# SCH_SEGEMENTOS_HORA_1.net
KiCad netlist of a schematic drawn in Altium Designer
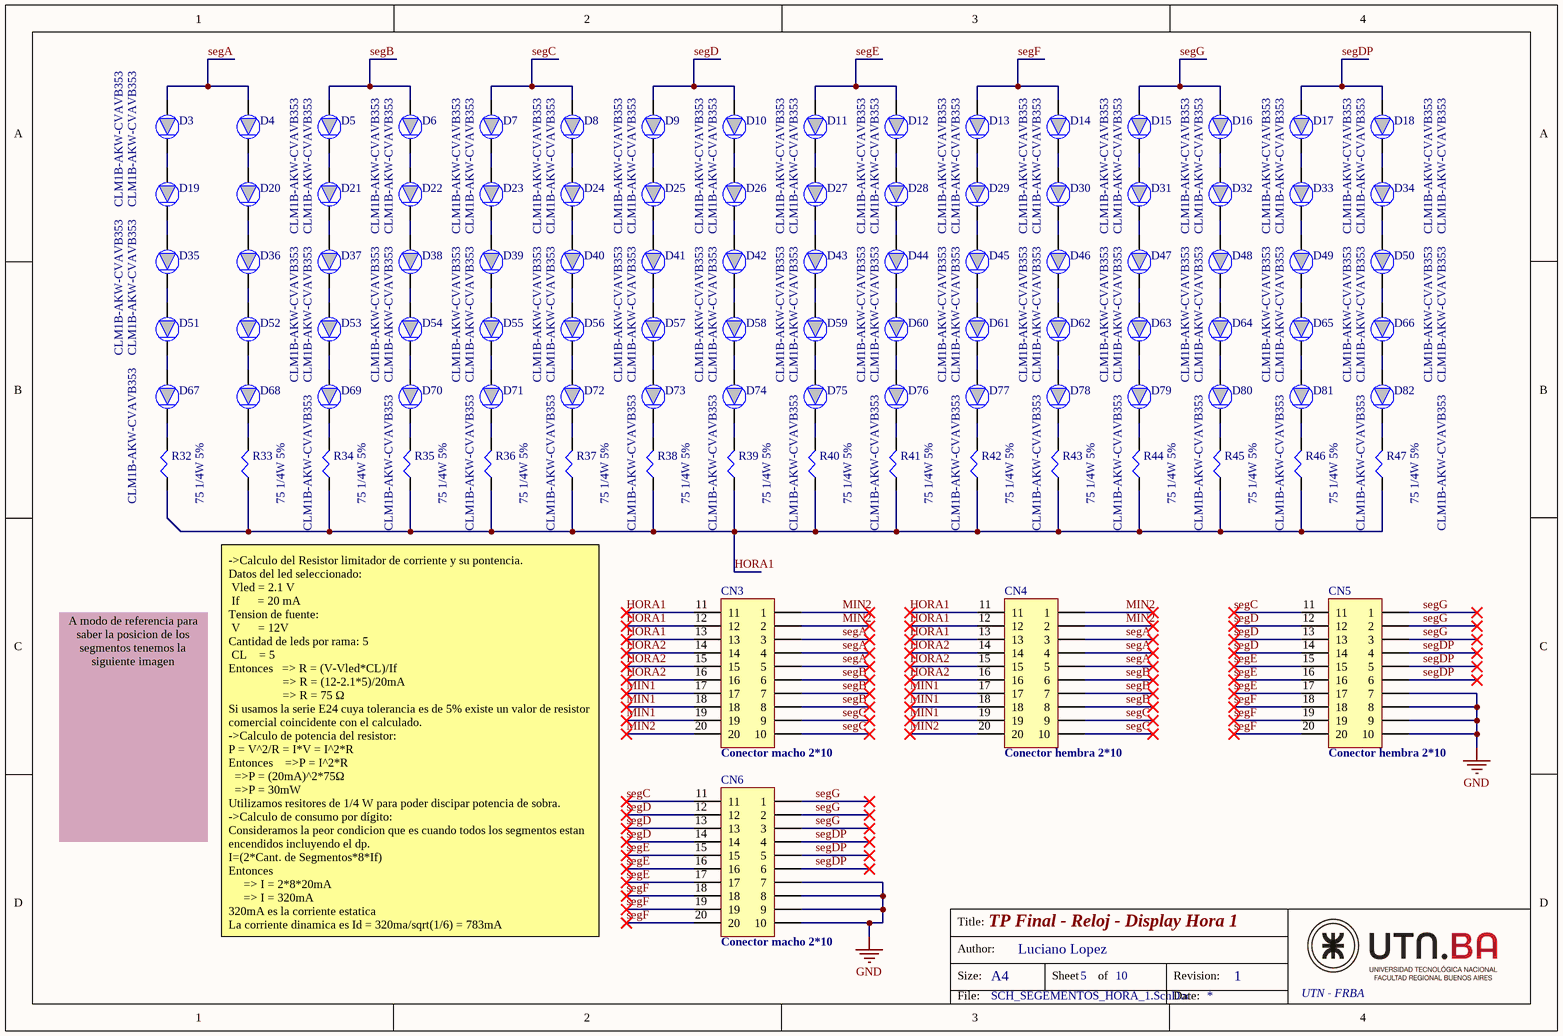
[diagram p0: SCH_SEGEMENTOS_HORA_1.SchDoc]

(export (version "E")
  (design (tool "Eeschema 10.0.6"))
  (components
    (comp (ref "CN3")
      (value "Conector macho 2*10")
      (description "Connector Generic 10 Vias")
      (libsource (lib "SCH_LIB") (part "CONN_2x10P"))
    )
    (comp (ref "CN4")
      (value "Conector hembra 2*10")
      (description "Connector Generic 10 Vias")
      (libsource (lib "SCH_LIB") (part "CONN_2x10P"))
    )
    (comp (ref "CN5")
      (value "Conector hembra 2*10")
      (description "Connector Generic 10 Vias")
      (libsource (lib "SCH_LIB") (part "CONN_2x10P"))
    )
    (comp (ref "CN6")
      (value "Conector macho 2*10")
      (description "Connector Generic 10 Vias")
      (libsource (lib "SCH_LIB") (part "CONN_2x10P"))
    )
    (comp (ref "D3")
      (value "CLM1B-AKW-CVAVB353")
      (footprint "PLCC2_LED")
      (libsource (lib "SCH_LIB") (part "LED_DIODE"))
    )
    (comp (ref "D4")
      (value "CLM1B-AKW-CVAVB353")
      (footprint "PLCC2_LED")
      (libsource (lib "SCH_LIB") (part "LED_DIODE"))
    )
    (comp (ref "D5")
      (value "CLM1B-AKW-CVAVB353")
      (footprint "PLCC2_LED")
      (libsource (lib "SCH_LIB") (part "LED_DIODE"))
    )
    (comp (ref "D6")
      (value "CLM1B-AKW-CVAVB353")
      (footprint "PLCC2_LED")
      (libsource (lib "SCH_LIB") (part "LED_DIODE"))
    )
    (comp (ref "D7")
      (value "CLM1B-AKW-CVAVB353")
      (footprint "PLCC2_LED")
      (libsource (lib "SCH_LIB") (part "LED_DIODE"))
    )
    (comp (ref "D8")
      (value "CLM1B-AKW-CVAVB353")
      (footprint "PLCC2_LED")
      (libsource (lib "SCH_LIB") (part "LED_DIODE"))
    )
    (comp (ref "D9")
      (value "CLM1B-AKW-CVAVB353")
      (footprint "PLCC2_LED")
      (libsource (lib "SCH_LIB") (part "LED_DIODE"))
    )
    (comp (ref "D10")
      (value "CLM1B-AKW-CVAVB353")
      (footprint "PLCC2_LED")
      (libsource (lib "SCH_LIB") (part "LED_DIODE"))
    )
    (comp (ref "D11")
      (value "CLM1B-AKW-CVAVB353")
      (footprint "PLCC2_LED")
      (libsource (lib "SCH_LIB") (part "LED_DIODE"))
    )
    (comp (ref "D12")
      (value "CLM1B-AKW-CVAVB353")
      (footprint "PLCC2_LED")
      (libsource (lib "SCH_LIB") (part "LED_DIODE"))
    )
    (comp (ref "D13")
      (value "CLM1B-AKW-CVAVB353")
      (footprint "PLCC2_LED")
      (libsource (lib "SCH_LIB") (part "LED_DIODE"))
    )
    (comp (ref "D14")
      (value "CLM1B-AKW-CVAVB353")
      (footprint "PLCC2_LED")
      (libsource (lib "SCH_LIB") (part "LED_DIODE"))
    )
    (comp (ref "D15")
      (value "CLM1B-AKW-CVAVB353")
      (footprint "PLCC2_LED")
      (libsource (lib "SCH_LIB") (part "LED_DIODE"))
    )
    (comp (ref "D16")
      (value "CLM1B-AKW-CVAVB353")
      (footprint "PLCC2_LED")
      (libsource (lib "SCH_LIB") (part "LED_DIODE"))
    )
    (comp (ref "D17")
      (value "CLM1B-AKW-CVAVB353")
      (footprint "PLCC2_LED")
      (libsource (lib "SCH_LIB") (part "LED_DIODE"))
    )
    (comp (ref "D18")
      (value "CLM1B-AKW-CVAVB353")
      (footprint "PLCC2_LED")
      (libsource (lib "SCH_LIB") (part "LED_DIODE"))
    )
    (comp (ref "D19")
      (value "CLM1B-AKW-CVAVB353")
      (footprint "PLCC2_LED")
      (libsource (lib "SCH_LIB") (part "LED_DIODE"))
    )
    (comp (ref "D20")
      (value "CLM1B-AKW-CVAVB353")
      (footprint "PLCC2_LED")
      (libsource (lib "SCH_LIB") (part "LED_DIODE"))
    )
    (comp (ref "D21")
      (value "CLM1B-AKW-CVAVB353")
      (footprint "PLCC2_LED")
      (libsource (lib "SCH_LIB") (part "LED_DIODE"))
    )
    (comp (ref "D22")
      (value "CLM1B-AKW-CVAVB353")
      (footprint "PLCC2_LED")
      (libsource (lib "SCH_LIB") (part "LED_DIODE"))
    )
    (comp (ref "D23")
      (value "CLM1B-AKW-CVAVB353")
      (footprint "PLCC2_LED")
      (libsource (lib "SCH_LIB") (part "LED_DIODE"))
    )
    (comp (ref "D24")
      (value "CLM1B-AKW-CVAVB353")
      (footprint "PLCC2_LED")
      (libsource (lib "SCH_LIB") (part "LED_DIODE"))
    )
    (comp (ref "D25")
      (value "CLM1B-AKW-CVAVB353")
      (footprint "PLCC2_LED")
      (libsource (lib "SCH_LIB") (part "LED_DIODE"))
    )
    (comp (ref "D26")
      (value "CLM1B-AKW-CVAVB353")
      (footprint "PLCC2_LED")
      (libsource (lib "SCH_LIB") (part "LED_DIODE"))
    )
    (comp (ref "D27")
      (value "CLM1B-AKW-CVAVB353")
      (footprint "PLCC2_LED")
      (libsource (lib "SCH_LIB") (part "LED_DIODE"))
    )
    (comp (ref "D28")
      (value "CLM1B-AKW-CVAVB353")
      (footprint "PLCC2_LED")
      (libsource (lib "SCH_LIB") (part "LED_DIODE"))
    )
    (comp (ref "D29")
      (value "CLM1B-AKW-CVAVB353")
      (footprint "PLCC2_LED")
      (libsource (lib "SCH_LIB") (part "LED_DIODE"))
    )
    (comp (ref "D30")
      (value "CLM1B-AKW-CVAVB353")
      (footprint "PLCC2_LED")
      (libsource (lib "SCH_LIB") (part "LED_DIODE"))
    )
    (comp (ref "D31")
      (value "CLM1B-AKW-CVAVB353")
      (footprint "PLCC2_LED")
      (libsource (lib "SCH_LIB") (part "LED_DIODE"))
    )
    (comp (ref "D32")
      (value "CLM1B-AKW-CVAVB353")
      (footprint "PLCC2_LED")
      (libsource (lib "SCH_LIB") (part "LED_DIODE"))
    )
    (comp (ref "D33")
      (value "CLM1B-AKW-CVAVB353")
      (footprint "PLCC2_LED")
      (libsource (lib "SCH_LIB") (part "LED_DIODE"))
    )
    (comp (ref "D34")
      (value "CLM1B-AKW-CVAVB353")
      (footprint "PLCC2_LED")
      (libsource (lib "SCH_LIB") (part "LED_DIODE"))
    )
    (comp (ref "D35")
      (value "CLM1B-AKW-CVAVB353")
      (footprint "PLCC2_LED")
      (libsource (lib "SCH_LIB") (part "LED_DIODE"))
    )
    (comp (ref "D36")
      (value "CLM1B-AKW-CVAVB353")
      (footprint "PLCC2_LED")
      (libsource (lib "SCH_LIB") (part "LED_DIODE"))
    )
    (comp (ref "D37")
      (value "CLM1B-AKW-CVAVB353")
      (footprint "PLCC2_LED")
      (libsource (lib "SCH_LIB") (part "LED_DIODE"))
    )
    (comp (ref "D38")
      (value "CLM1B-AKW-CVAVB353")
      (footprint "PLCC2_LED")
      (libsource (lib "SCH_LIB") (part "LED_DIODE"))
    )
    (comp (ref "D39")
      (value "CLM1B-AKW-CVAVB353")
      (footprint "PLCC2_LED")
      (libsource (lib "SCH_LIB") (part "LED_DIODE"))
    )
    (comp (ref "D40")
      (value "CLM1B-AKW-CVAVB353")
      (footprint "PLCC2_LED")
      (libsource (lib "SCH_LIB") (part "LED_DIODE"))
    )
    (comp (ref "D41")
      (value "CLM1B-AKW-CVAVB353")
      (footprint "PLCC2_LED")
      (libsource (lib "SCH_LIB") (part "LED_DIODE"))
    )
    (comp (ref "D42")
      (value "CLM1B-AKW-CVAVB353")
      (footprint "PLCC2_LED")
      (libsource (lib "SCH_LIB") (part "LED_DIODE"))
    )
    (comp (ref "D43")
      (value "CLM1B-AKW-CVAVB353")
      (footprint "PLCC2_LED")
      (libsource (lib "SCH_LIB") (part "LED_DIODE"))
    )
    (comp (ref "D44")
      (value "CLM1B-AKW-CVAVB353")
      (footprint "PLCC2_LED")
      (libsource (lib "SCH_LIB") (part "LED_DIODE"))
    )
    (comp (ref "D45")
      (value "CLM1B-AKW-CVAVB353")
      (footprint "PLCC2_LED")
      (libsource (lib "SCH_LIB") (part "LED_DIODE"))
    )
    (comp (ref "D46")
      (value "CLM1B-AKW-CVAVB353")
      (footprint "PLCC2_LED")
      (libsource (lib "SCH_LIB") (part "LED_DIODE"))
    )
    (comp (ref "D47")
      (value "CLM1B-AKW-CVAVB353")
      (footprint "PLCC2_LED")
      (libsource (lib "SCH_LIB") (part "LED_DIODE"))
    )
    (comp (ref "D48")
      (value "CLM1B-AKW-CVAVB353")
      (footprint "PLCC2_LED")
      (libsource (lib "SCH_LIB") (part "LED_DIODE"))
    )
    (comp (ref "D49")
      (value "CLM1B-AKW-CVAVB353")
      (footprint "PLCC2_LED")
      (libsource (lib "SCH_LIB") (part "LED_DIODE"))
    )
    (comp (ref "D50")
      (value "CLM1B-AKW-CVAVB353")
      (footprint "PLCC2_LED")
      (libsource (lib "SCH_LIB") (part "LED_DIODE"))
    )
    (comp (ref "D51")
      (value "CLM1B-AKW-CVAVB353")
      (footprint "PLCC2_LED")
      (libsource (lib "SCH_LIB") (part "LED_DIODE"))
    )
    (comp (ref "D52")
      (value "CLM1B-AKW-CVAVB353")
      (footprint "PLCC2_LED")
      (libsource (lib "SCH_LIB") (part "LED_DIODE"))
    )
    (comp (ref "D53")
      (value "CLM1B-AKW-CVAVB353")
      (footprint "PLCC2_LED")
      (libsource (lib "SCH_LIB") (part "LED_DIODE"))
    )
    (comp (ref "D54")
      (value "CLM1B-AKW-CVAVB353")
      (footprint "PLCC2_LED")
      (libsource (lib "SCH_LIB") (part "LED_DIODE"))
    )
    (comp (ref "D55")
      (value "CLM1B-AKW-CVAVB353")
      (footprint "PLCC2_LED")
      (libsource (lib "SCH_LIB") (part "LED_DIODE"))
    )
    (comp (ref "D56")
      (value "CLM1B-AKW-CVAVB353")
      (footprint "PLCC2_LED")
      (libsource (lib "SCH_LIB") (part "LED_DIODE"))
    )
    (comp (ref "D57")
      (value "CLM1B-AKW-CVAVB353")
      (footprint "PLCC2_LED")
      (libsource (lib "SCH_LIB") (part "LED_DIODE"))
    )
    (comp (ref "D58")
      (value "CLM1B-AKW-CVAVB353")
      (footprint "PLCC2_LED")
      (libsource (lib "SCH_LIB") (part "LED_DIODE"))
    )
    (comp (ref "D59")
      (value "CLM1B-AKW-CVAVB353")
      (footprint "PLCC2_LED")
      (libsource (lib "SCH_LIB") (part "LED_DIODE"))
    )
    (comp (ref "D60")
      (value "CLM1B-AKW-CVAVB353")
      (footprint "PLCC2_LED")
      (libsource (lib "SCH_LIB") (part "LED_DIODE"))
    )
    (comp (ref "D61")
      (value "CLM1B-AKW-CVAVB353")
      (footprint "PLCC2_LED")
      (libsource (lib "SCH_LIB") (part "LED_DIODE"))
    )
    (comp (ref "D62")
      (value "CLM1B-AKW-CVAVB353")
      (footprint "PLCC2_LED")
      (libsource (lib "SCH_LIB") (part "LED_DIODE"))
    )
    (comp (ref "D63")
      (value "CLM1B-AKW-CVAVB353")
      (footprint "PLCC2_LED")
      (libsource (lib "SCH_LIB") (part "LED_DIODE"))
    )
    (comp (ref "D64")
      (value "CLM1B-AKW-CVAVB353")
      (footprint "PLCC2_LED")
      (libsource (lib "SCH_LIB") (part "LED_DIODE"))
    )
    (comp (ref "D65")
      (value "CLM1B-AKW-CVAVB353")
      (footprint "PLCC2_LED")
      (libsource (lib "SCH_LIB") (part "LED_DIODE"))
    )
    (comp (ref "D66")
      (value "CLM1B-AKW-CVAVB353")
      (footprint "PLCC2_LED")
      (libsource (lib "SCH_LIB") (part "LED_DIODE"))
    )
    (comp (ref "D67")
      (value "CLM1B-AKW-CVAVB353")
      (footprint "PLCC2_LED")
      (libsource (lib "SCH_LIB") (part "LED_DIODE"))
    )
    (comp (ref "D68")
      (value "CLM1B-AKW-CVAVB353")
      (footprint "PLCC2_LED")
      (libsource (lib "SCH_LIB") (part "LED_DIODE"))
    )
    (comp (ref "D69")
      (value "CLM1B-AKW-CVAVB353")
      (footprint "PLCC2_LED")
      (libsource (lib "SCH_LIB") (part "LED_DIODE"))
    )
    (comp (ref "D70")
      (value "CLM1B-AKW-CVAVB353")
      (footprint "PLCC2_LED")
      (libsource (lib "SCH_LIB") (part "LED_DIODE"))
    )
    (comp (ref "D71")
      (value "CLM1B-AKW-CVAVB353")
      (footprint "PLCC2_LED")
      (libsource (lib "SCH_LIB") (part "LED_DIODE"))
    )
    (comp (ref "D72")
      (value "CLM1B-AKW-CVAVB353")
      (footprint "PLCC2_LED")
      (libsource (lib "SCH_LIB") (part "LED_DIODE"))
    )
    (comp (ref "D73")
      (value "CLM1B-AKW-CVAVB353")
      (footprint "PLCC2_LED")
      (libsource (lib "SCH_LIB") (part "LED_DIODE"))
    )
    (comp (ref "D74")
      (value "CLM1B-AKW-CVAVB353")
      (footprint "PLCC2_LED")
      (libsource (lib "SCH_LIB") (part "LED_DIODE"))
    )
    (comp (ref "D75")
      (value "CLM1B-AKW-CVAVB353")
      (footprint "PLCC2_LED")
      (libsource (lib "SCH_LIB") (part "LED_DIODE"))
    )
    (comp (ref "D76")
      (value "CLM1B-AKW-CVAVB353")
      (footprint "PLCC2_LED")
      (libsource (lib "SCH_LIB") (part "LED_DIODE"))
    )
    (comp (ref "D77")
      (value "CLM1B-AKW-CVAVB353")
      (footprint "PLCC2_LED")
      (libsource (lib "SCH_LIB") (part "LED_DIODE"))
    )
    (comp (ref "D78")
      (value "CLM1B-AKW-CVAVB353")
      (footprint "PLCC2_LED")
      (libsource (lib "SCH_LIB") (part "LED_DIODE"))
    )
    (comp (ref "D79")
      (value "CLM1B-AKW-CVAVB353")
      (footprint "PLCC2_LED")
      (libsource (lib "SCH_LIB") (part "LED_DIODE"))
    )
    (comp (ref "D80")
      (value "CLM1B-AKW-CVAVB353")
      (footprint "PLCC2_LED")
      (libsource (lib "SCH_LIB") (part "LED_DIODE"))
    )
    (comp (ref "D81")
      (value "CLM1B-AKW-CVAVB353")
      (footprint "PLCC2_LED")
      (libsource (lib "SCH_LIB") (part "LED_DIODE"))
    )
    (comp (ref "D82")
      (value "CLM1B-AKW-CVAVB353")
      (footprint "PLCC2_LED")
      (libsource (lib "SCH_LIB") (part "LED_DIODE"))
    )
    (comp (ref "R32") (value "75 1/4W 5%") (footprint "R_0805") (libsource (lib "SCH_LIB") (part "Resistor")))
    (comp (ref "R33") (value "75 1/4W 5%") (footprint "R_0805") (libsource (lib "SCH_LIB") (part "Resistor")))
    (comp (ref "R34") (value "75 1/4W 5%") (footprint "R_0805") (libsource (lib "SCH_LIB") (part "Resistor")))
    (comp (ref "R35") (value "75 1/4W 5%") (footprint "R_0805") (libsource (lib "SCH_LIB") (part "Resistor")))
    (comp (ref "R36") (value "75 1/4W 5%") (footprint "R_0805") (libsource (lib "SCH_LIB") (part "Resistor")))
    (comp (ref "R37") (value "75 1/4W 5%") (footprint "R_0805") (libsource (lib "SCH_LIB") (part "Resistor")))
    (comp (ref "R38") (value "75 1/4W 5%") (footprint "R_0805") (libsource (lib "SCH_LIB") (part "Resistor")))
    (comp (ref "R39") (value "75 1/4W 5%") (footprint "R_0805") (libsource (lib "SCH_LIB") (part "Resistor")))
    (comp (ref "R40") (value "75 1/4W 5%") (footprint "R_0805") (libsource (lib "SCH_LIB") (part "Resistor")))
    (comp (ref "R41") (value "75 1/4W 5%") (footprint "R_0805") (libsource (lib "SCH_LIB") (part "Resistor")))
    (comp (ref "R42") (value "75 1/4W 5%") (footprint "R_0805") (libsource (lib "SCH_LIB") (part "Resistor")))
    (comp (ref "R43") (value "75 1/4W 5%") (footprint "R_0805") (libsource (lib "SCH_LIB") (part "Resistor")))
    (comp (ref "R44") (value "75 1/4W 5%") (footprint "R_0805") (libsource (lib "SCH_LIB") (part "Resistor")))
    (comp (ref "R45") (value "75 1/4W 5%") (footprint "R_0805") (libsource (lib "SCH_LIB") (part "Resistor")))
    (comp (ref "R46") (value "75 1/4W 5%") (footprint "R_0805") (libsource (lib "SCH_LIB") (part "Resistor")))
    (comp (ref "R47") (value "75 1/4W 5%") (footprint "R_0805") (libsource (lib "SCH_LIB") (part "Resistor")))
  )
  (nets
    (net (code "1") (name "/HORA1") (class "Default")
      (node (ref "CN3") (pin "11") (pinfunction "11_11") (pintype "passive"))
      (node (ref "CN3") (pin "12") (pinfunction "12_12") (pintype "passive"))
      (node (ref "CN3") (pin "13") (pinfunction "13_13") (pintype "passive"))
      (node (ref "CN4") (pin "11") (pinfunction "11_11") (pintype "passive"))
      (node (ref "CN4") (pin "12") (pinfunction "12_12") (pintype "passive"))
      (node (ref "CN4") (pin "13") (pinfunction "13_13") (pintype "passive"))
      (node (ref "R32") (pin "47") (pinfunction "47_47") (pintype "passive"))
      (node (ref "R33") (pin "47") (pinfunction "47_47") (pintype "passive"))
      (node (ref "R34") (pin "47") (pinfunction "47_47") (pintype "passive"))
      (node (ref "R35") (pin "47") (pinfunction "47_47") (pintype "passive"))
      (node (ref "R36") (pin "47") (pinfunction "47_47") (pintype "passive"))
      (node (ref "R37") (pin "47") (pinfunction "47_47") (pintype "passive"))
      (node (ref "R38") (pin "47") (pinfunction "47_47") (pintype "passive"))
      (node (ref "R39") (pin "47") (pinfunction "47_47") (pintype "passive"))
      (node (ref "R40") (pin "47") (pinfunction "47_47") (pintype "passive"))
      (node (ref "R41") (pin "47") (pinfunction "47_47") (pintype "passive"))
      (node (ref "R42") (pin "47") (pinfunction "47_47") (pintype "passive"))
      (node (ref "R43") (pin "47") (pinfunction "47_47") (pintype "passive"))
      (node (ref "R44") (pin "47") (pinfunction "47_47") (pintype "passive"))
      (node (ref "R45") (pin "47") (pinfunction "47_47") (pintype "passive"))
      (node (ref "R46") (pin "47") (pinfunction "47_47") (pintype "passive"))
      (node (ref "R47") (pin "47") (pinfunction "47_47") (pintype "passive"))
    )
    (net (code "2") (name "/HORA2") (class "Default")
      (node (ref "CN3") (pin "14") (pinfunction "14_14") (pintype "passive"))
      (node (ref "CN3") (pin "15") (pinfunction "15_15") (pintype "passive"))
      (node (ref "CN3") (pin "16") (pinfunction "16_16") (pintype "passive"))
      (node (ref "CN4") (pin "14") (pinfunction "14_14") (pintype "passive"))
      (node (ref "CN4") (pin "15") (pinfunction "15_15") (pintype "passive"))
      (node (ref "CN4") (pin "16") (pinfunction "16_16") (pintype "passive"))
    )
    (net (code "3") (name "/MIN1") (class "Default")
      (node (ref "CN3") (pin "17") (pinfunction "17_17") (pintype "passive"))
      (node (ref "CN3") (pin "18") (pinfunction "18_18") (pintype "passive"))
      (node (ref "CN3") (pin "19") (pinfunction "19_19") (pintype "passive"))
      (node (ref "CN4") (pin "17") (pinfunction "17_17") (pintype "passive"))
      (node (ref "CN4") (pin "18") (pinfunction "18_18") (pintype "passive"))
      (node (ref "CN4") (pin "19") (pinfunction "19_19") (pintype "passive"))
    )
    (net (code "4") (name "/MIN2") (class "Default")
      (node (ref "CN3") (pin "1") (pinfunction "1_1") (pintype "passive"))
      (node (ref "CN3") (pin "2") (pinfunction "2_2") (pintype "passive"))
      (node (ref "CN3") (pin "20") (pinfunction "20_20") (pintype "passive"))
      (node (ref "CN4") (pin "1") (pinfunction "1_1") (pintype "passive"))
      (node (ref "CN4") (pin "2") (pinfunction "2_2") (pintype "passive"))
      (node (ref "CN4") (pin "20") (pinfunction "20_20") (pintype "passive"))
    )
    (net (code "5") (name "/segA") (class "Default")
      (node (ref "CN3") (pin "3") (pinfunction "3_3") (pintype "passive"))
      (node (ref "CN3") (pin "4") (pinfunction "4_4") (pintype "passive"))
      (node (ref "CN3") (pin "5") (pinfunction "5_5") (pintype "passive"))
      (node (ref "CN4") (pin "3") (pinfunction "3_3") (pintype "passive"))
      (node (ref "CN4") (pin "4") (pinfunction "4_4") (pintype "passive"))
      (node (ref "CN4") (pin "5") (pinfunction "5_5") (pintype "passive"))
      (node (ref "D3") (pin "12") (pinfunction "12_12") (pintype "passive"))
      (node (ref "D4") (pin "12") (pinfunction "12_12") (pintype "passive"))
    )
    (net (code "6") (name "/segB") (class "Default")
      (node (ref "CN3") (pin "6") (pinfunction "6_6") (pintype "passive"))
      (node (ref "CN3") (pin "7") (pinfunction "7_7") (pintype "passive"))
      (node (ref "CN3") (pin "8") (pinfunction "8_8") (pintype "passive"))
      (node (ref "CN4") (pin "6") (pinfunction "6_6") (pintype "passive"))
      (node (ref "CN4") (pin "7") (pinfunction "7_7") (pintype "passive"))
      (node (ref "CN4") (pin "8") (pinfunction "8_8") (pintype "passive"))
      (node (ref "D5") (pin "12") (pinfunction "12_12") (pintype "passive"))
      (node (ref "D6") (pin "12") (pinfunction "12_12") (pintype "passive"))
    )
    (net (code "7") (name "/segC") (class "Default")
      (node (ref "CN3") (pin "10") (pinfunction "10_10") (pintype "passive"))
      (node (ref "CN3") (pin "9") (pinfunction "9_9") (pintype "passive"))
      (node (ref "CN4") (pin "10") (pinfunction "10_10") (pintype "passive"))
      (node (ref "CN4") (pin "9") (pinfunction "9_9") (pintype "passive"))
      (node (ref "CN5") (pin "11") (pinfunction "11_11") (pintype "passive"))
      (node (ref "CN6") (pin "11") (pinfunction "11_11") (pintype "passive"))
      (node (ref "D7") (pin "12") (pinfunction "12_12") (pintype "passive"))
      (node (ref "D8") (pin "12") (pinfunction "12_12") (pintype "passive"))
    )
    (net (code "8") (name "/segD") (class "Default")
      (node (ref "CN5") (pin "12") (pinfunction "12_12") (pintype "passive"))
      (node (ref "CN5") (pin "13") (pinfunction "13_13") (pintype "passive"))
      (node (ref "CN5") (pin "14") (pinfunction "14_14") (pintype "passive"))
      (node (ref "CN6") (pin "12") (pinfunction "12_12") (pintype "passive"))
      (node (ref "CN6") (pin "13") (pinfunction "13_13") (pintype "passive"))
      (node (ref "CN6") (pin "14") (pinfunction "14_14") (pintype "passive"))
      (node (ref "D10") (pin "12") (pinfunction "12_12") (pintype "passive"))
      (node (ref "D9") (pin "12") (pinfunction "12_12") (pintype "passive"))
    )
    (net (code "9") (name "/segDP") (class "Default")
      (node (ref "CN5") (pin "4") (pinfunction "4_4") (pintype "passive"))
      (node (ref "CN5") (pin "5") (pinfunction "5_5") (pintype "passive"))
      (node (ref "CN5") (pin "6") (pinfunction "6_6") (pintype "passive"))
      (node (ref "CN6") (pin "4") (pinfunction "4_4") (pintype "passive"))
      (node (ref "CN6") (pin "5") (pinfunction "5_5") (pintype "passive"))
      (node (ref "CN6") (pin "6") (pinfunction "6_6") (pintype "passive"))
      (node (ref "D17") (pin "12") (pinfunction "12_12") (pintype "passive"))
      (node (ref "D18") (pin "12") (pinfunction "12_12") (pintype "passive"))
    )
    (net (code "10") (name "/segE") (class "Default")
      (node (ref "CN5") (pin "15") (pinfunction "15_15") (pintype "passive"))
      (node (ref "CN5") (pin "16") (pinfunction "16_16") (pintype "passive"))
      (node (ref "CN5") (pin "17") (pinfunction "17_17") (pintype "passive"))
      (node (ref "CN6") (pin "15") (pinfunction "15_15") (pintype "passive"))
      (node (ref "CN6") (pin "16") (pinfunction "16_16") (pintype "passive"))
      (node (ref "CN6") (pin "17") (pinfunction "17_17") (pintype "passive"))
      (node (ref "D11") (pin "12") (pinfunction "12_12") (pintype "passive"))
      (node (ref "D12") (pin "12") (pinfunction "12_12") (pintype "passive"))
    )
    (net (code "11") (name "/segF") (class "Default")
      (node (ref "CN5") (pin "18") (pinfunction "18_18") (pintype "passive"))
      (node (ref "CN5") (pin "19") (pinfunction "19_19") (pintype "passive"))
      (node (ref "CN5") (pin "20") (pinfunction "20_20") (pintype "passive"))
      (node (ref "CN6") (pin "18") (pinfunction "18_18") (pintype "passive"))
      (node (ref "CN6") (pin "19") (pinfunction "19_19") (pintype "passive"))
      (node (ref "CN6") (pin "20") (pinfunction "20_20") (pintype "passive"))
      (node (ref "D13") (pin "12") (pinfunction "12_12") (pintype "passive"))
      (node (ref "D14") (pin "12") (pinfunction "12_12") (pintype "passive"))
    )
    (net (code "12") (name "/segG") (class "Default")
      (node (ref "CN5") (pin "1") (pinfunction "1_1") (pintype "passive"))
      (node (ref "CN5") (pin "2") (pinfunction "2_2") (pintype "passive"))
      (node (ref "CN5") (pin "3") (pinfunction "3_3") (pintype "passive"))
      (node (ref "CN6") (pin "1") (pinfunction "1_1") (pintype "passive"))
      (node (ref "CN6") (pin "2") (pinfunction "2_2") (pintype "passive"))
      (node (ref "CN6") (pin "3") (pinfunction "3_3") (pintype "passive"))
      (node (ref "D15") (pin "12") (pinfunction "12_12") (pintype "passive"))
      (node (ref "D16") (pin "12") (pinfunction "12_12") (pintype "passive"))
    )
    (net (code "13") (name "GND") (class "Default")
      (node (ref "CN5") (pin "10") (pinfunction "10_10") (pintype "passive"))
      (node (ref "CN5") (pin "7") (pinfunction "7_7") (pintype "passive"))
      (node (ref "CN5") (pin "8") (pinfunction "8_8") (pintype "passive"))
      (node (ref "CN5") (pin "9") (pinfunction "9_9") (pintype "passive"))
      (node (ref "CN6") (pin "10") (pinfunction "10_10") (pintype "passive"))
      (node (ref "CN6") (pin "7") (pinfunction "7_7") (pintype "passive"))
      (node (ref "CN6") (pin "8") (pinfunction "8_8") (pintype "passive"))
      (node (ref "CN6") (pin "9") (pinfunction "9_9") (pintype "passive"))
    )
    (net (code "14") (name "Net-(D10-Pad11)") (class "Default")
      (node (ref "D10") (pin "11") (pinfunction "11_11") (pintype "passive"))
      (node (ref "D26") (pin "12") (pinfunction "12_12") (pintype "passive"))
    )
    (net (code "15") (name "Net-(D11-Pad11)") (class "Default")
      (node (ref "D11") (pin "11") (pinfunction "11_11") (pintype "passive"))
      (node (ref "D27") (pin "12") (pinfunction "12_12") (pintype "passive"))
    )
    (net (code "16") (name "Net-(D12-Pad11)") (class "Default")
      (node (ref "D12") (pin "11") (pinfunction "11_11") (pintype "passive"))
      (node (ref "D28") (pin "12") (pinfunction "12_12") (pintype "passive"))
    )
    (net (code "17") (name "Net-(D13-Pad11)") (class "Default")
      (node (ref "D13") (pin "11") (pinfunction "11_11") (pintype "passive"))
      (node (ref "D29") (pin "12") (pinfunction "12_12") (pintype "passive"))
    )
    (net (code "18") (name "Net-(D14-Pad11)") (class "Default")
      (node (ref "D14") (pin "11") (pinfunction "11_11") (pintype "passive"))
      (node (ref "D30") (pin "12") (pinfunction "12_12") (pintype "passive"))
    )
    (net (code "19") (name "Net-(D15-Pad11)") (class "Default")
      (node (ref "D15") (pin "11") (pinfunction "11_11") (pintype "passive"))
      (node (ref "D31") (pin "12") (pinfunction "12_12") (pintype "passive"))
    )
    (net (code "20") (name "Net-(D16-Pad11)") (class "Default")
      (node (ref "D16") (pin "11") (pinfunction "11_11") (pintype "passive"))
      (node (ref "D32") (pin "12") (pinfunction "12_12") (pintype "passive"))
    )
    (net (code "21") (name "Net-(D17-Pad11)") (class "Default")
      (node (ref "D17") (pin "11") (pinfunction "11_11") (pintype "passive"))
      (node (ref "D33") (pin "12") (pinfunction "12_12") (pintype "passive"))
    )
    (net (code "22") (name "Net-(D18-Pad11)") (class "Default")
      (node (ref "D18") (pin "11") (pinfunction "11_11") (pintype "passive"))
      (node (ref "D34") (pin "12") (pinfunction "12_12") (pintype "passive"))
    )
    (net (code "23") (name "Net-(D19-Pad11)") (class "Default")
      (node (ref "D19") (pin "11") (pinfunction "11_11") (pintype "passive"))
      (node (ref "D35") (pin "12") (pinfunction "12_12") (pintype "passive"))
    )
    (net (code "24") (name "Net-(D19-Pad12)") (class "Default")
      (node (ref "D19") (pin "12") (pinfunction "12_12") (pintype "passive"))
      (node (ref "D3") (pin "11") (pinfunction "11_11") (pintype "passive"))
    )
    (net (code "25") (name "Net-(D20-Pad11)") (class "Default")
      (node (ref "D20") (pin "11") (pinfunction "11_11") (pintype "passive"))
      (node (ref "D36") (pin "12") (pinfunction "12_12") (pintype "passive"))
    )
    (net (code "26") (name "Net-(D20-Pad12)") (class "Default")
      (node (ref "D20") (pin "12") (pinfunction "12_12") (pintype "passive"))
      (node (ref "D4") (pin "11") (pinfunction "11_11") (pintype "passive"))
    )
    (net (code "27") (name "Net-(D21-Pad11)") (class "Default")
      (node (ref "D21") (pin "11") (pinfunction "11_11") (pintype "passive"))
      (node (ref "D37") (pin "12") (pinfunction "12_12") (pintype "passive"))
    )
    (net (code "28") (name "Net-(D21-Pad12)") (class "Default")
      (node (ref "D21") (pin "12") (pinfunction "12_12") (pintype "passive"))
      (node (ref "D5") (pin "11") (pinfunction "11_11") (pintype "passive"))
    )
    (net (code "29") (name "Net-(D22-Pad11)") (class "Default")
      (node (ref "D22") (pin "11") (pinfunction "11_11") (pintype "passive"))
      (node (ref "D38") (pin "12") (pinfunction "12_12") (pintype "passive"))
    )
    (net (code "30") (name "Net-(D22-Pad12)") (class "Default")
      (node (ref "D22") (pin "12") (pinfunction "12_12") (pintype "passive"))
      (node (ref "D6") (pin "11") (pinfunction "11_11") (pintype "passive"))
    )
    (net (code "31") (name "Net-(D23-Pad11)") (class "Default")
      (node (ref "D23") (pin "11") (pinfunction "11_11") (pintype "passive"))
      (node (ref "D39") (pin "12") (pinfunction "12_12") (pintype "passive"))
    )
    (net (code "32") (name "Net-(D23-Pad12)") (class "Default")
      (node (ref "D23") (pin "12") (pinfunction "12_12") (pintype "passive"))
      (node (ref "D7") (pin "11") (pinfunction "11_11") (pintype "passive"))
    )
    (net (code "33") (name "Net-(D24-Pad11)") (class "Default")
      (node (ref "D24") (pin "11") (pinfunction "11_11") (pintype "passive"))
      (node (ref "D40") (pin "12") (pinfunction "12_12") (pintype "passive"))
    )
    (net (code "34") (name "Net-(D24-Pad12)") (class "Default")
      (node (ref "D24") (pin "12") (pinfunction "12_12") (pintype "passive"))
      (node (ref "D8") (pin "11") (pinfunction "11_11") (pintype "passive"))
    )
    (net (code "35") (name "Net-(D25-Pad11)") (class "Default")
      (node (ref "D25") (pin "11") (pinfunction "11_11") (pintype "passive"))
      (node (ref "D41") (pin "12") (pinfunction "12_12") (pintype "passive"))
    )
    (net (code "36") (name "Net-(D25-Pad12)") (class "Default")
      (node (ref "D25") (pin "12") (pinfunction "12_12") (pintype "passive"))
      (node (ref "D9") (pin "11") (pinfunction "11_11") (pintype "passive"))
    )
    (net (code "37") (name "Net-(D26-Pad11)") (class "Default")
      (node (ref "D26") (pin "11") (pinfunction "11_11") (pintype "passive"))
      (node (ref "D42") (pin "12") (pinfunction "12_12") (pintype "passive"))
    )
    (net (code "38") (name "Net-(D27-Pad11)") (class "Default")
      (node (ref "D27") (pin "11") (pinfunction "11_11") (pintype "passive"))
      (node (ref "D43") (pin "12") (pinfunction "12_12") (pintype "passive"))
    )
    (net (code "39") (name "Net-(D28-Pad11)") (class "Default")
      (node (ref "D28") (pin "11") (pinfunction "11_11") (pintype "passive"))
      (node (ref "D44") (pin "12") (pinfunction "12_12") (pintype "passive"))
    )
    (net (code "40") (name "Net-(D29-Pad11)") (class "Default")
      (node (ref "D29") (pin "11") (pinfunction "11_11") (pintype "passive"))
      (node (ref "D45") (pin "12") (pinfunction "12_12") (pintype "passive"))
    )
    (net (code "41") (name "Net-(D30-Pad11)") (class "Default")
      (node (ref "D30") (pin "11") (pinfunction "11_11") (pintype "passive"))
      (node (ref "D46") (pin "12") (pinfunction "12_12") (pintype "passive"))
    )
    (net (code "42") (name "Net-(D31-Pad11)") (class "Default")
      (node (ref "D31") (pin "11") (pinfunction "11_11") (pintype "passive"))
      (node (ref "D47") (pin "12") (pinfunction "12_12") (pintype "passive"))
    )
    (net (code "43") (name "Net-(D32-Pad11)") (class "Default")
      (node (ref "D32") (pin "11") (pinfunction "11_11") (pintype "passive"))
      (node (ref "D48") (pin "12") (pinfunction "12_12") (pintype "passive"))
    )
    (net (code "44") (name "Net-(D33-Pad11)") (class "Default")
      (node (ref "D33") (pin "11") (pinfunction "11_11") (pintype "passive"))
      (node (ref "D49") (pin "12") (pinfunction "12_12") (pintype "passive"))
    )
    (net (code "45") (name "Net-(D34-Pad11)") (class "Default")
      (node (ref "D34") (pin "11") (pinfunction "11_11") (pintype "passive"))
      (node (ref "D50") (pin "12") (pinfunction "12_12") (pintype "passive"))
    )
    (net (code "46") (name "Net-(D35-Pad11)") (class "Default")
      (node (ref "D35") (pin "11") (pinfunction "11_11") (pintype "passive"))
      (node (ref "D51") (pin "12") (pinfunction "12_12") (pintype "passive"))
    )
    (net (code "47") (name "Net-(D36-Pad11)") (class "Default")
      (node (ref "D36") (pin "11") (pinfunction "11_11") (pintype "passive"))
      (node (ref "D52") (pin "12") (pinfunction "12_12") (pintype "passive"))
    )
    (net (code "48") (name "Net-(D37-Pad11)") (class "Default")
      (node (ref "D37") (pin "11") (pinfunction "11_11") (pintype "passive"))
      (node (ref "D53") (pin "12") (pinfunction "12_12") (pintype "passive"))
    )
    (net (code "49") (name "Net-(D38-Pad11)") (class "Default")
      (node (ref "D38") (pin "11") (pinfunction "11_11") (pintype "passive"))
      (node (ref "D54") (pin "12") (pinfunction "12_12") (pintype "passive"))
    )
    (net (code "50") (name "Net-(D39-Pad11)") (class "Default")
      (node (ref "D39") (pin "11") (pinfunction "11_11") (pintype "passive"))
      (node (ref "D55") (pin "12") (pinfunction "12_12") (pintype "passive"))
    )
    (net (code "51") (name "Net-(D40-Pad11)") (class "Default")
      (node (ref "D40") (pin "11") (pinfunction "11_11") (pintype "passive"))
      (node (ref "D56") (pin "12") (pinfunction "12_12") (pintype "passive"))
    )
    (net (code "52") (name "Net-(D41-Pad11)") (class "Default")
      (node (ref "D41") (pin "11") (pinfunction "11_11") (pintype "passive"))
      (node (ref "D57") (pin "12") (pinfunction "12_12") (pintype "passive"))
    )
    (net (code "53") (name "Net-(D42-Pad11)") (class "Default")
      (node (ref "D42") (pin "11") (pinfunction "11_11") (pintype "passive"))
      (node (ref "D58") (pin "12") (pinfunction "12_12") (pintype "passive"))
    )
    (net (code "54") (name "Net-(D43-Pad11)") (class "Default")
      (node (ref "D43") (pin "11") (pinfunction "11_11") (pintype "passive"))
      (node (ref "D59") (pin "12") (pinfunction "12_12") (pintype "passive"))
    )
    (net (code "55") (name "Net-(D44-Pad11)") (class "Default")
      (node (ref "D44") (pin "11") (pinfunction "11_11") (pintype "passive"))
      (node (ref "D60") (pin "12") (pinfunction "12_12") (pintype "passive"))
    )
    (net (code "56") (name "Net-(D45-Pad11)") (class "Default")
      (node (ref "D45") (pin "11") (pinfunction "11_11") (pintype "passive"))
      (node (ref "D61") (pin "12") (pinfunction "12_12") (pintype "passive"))
    )
    (net (code "57") (name "Net-(D46-Pad11)") (class "Default")
      (node (ref "D46") (pin "11") (pinfunction "11_11") (pintype "passive"))
      (node (ref "D62") (pin "12") (pinfunction "12_12") (pintype "passive"))
    )
    (net (code "58") (name "Net-(D47-Pad11)") (class "Default")
      (node (ref "D47") (pin "11") (pinfunction "11_11") (pintype "passive"))
      (node (ref "D63") (pin "12") (pinfunction "12_12") (pintype "passive"))
    )
    (net (code "59") (name "Net-(D48-Pad11)") (class "Default")
      (node (ref "D48") (pin "11") (pinfunction "11_11") (pintype "passive"))
      (node (ref "D64") (pin "12") (pinfunction "12_12") (pintype "passive"))
    )
    (net (code "60") (name "Net-(D49-Pad11)") (class "Default")
      (node (ref "D49") (pin "11") (pinfunction "11_11") (pintype "passive"))
      (node (ref "D65") (pin "12") (pinfunction "12_12") (pintype "passive"))
    )
    (net (code "61") (name "Net-(D50-Pad11)") (class "Default")
      (node (ref "D50") (pin "11") (pinfunction "11_11") (pintype "passive"))
      (node (ref "D66") (pin "12") (pinfunction "12_12") (pintype "passive"))
    )
    (net (code "62") (name "Net-(D51-Pad11)") (class "Default")
      (node (ref "D51") (pin "11") (pinfunction "11_11") (pintype "passive"))
      (node (ref "D67") (pin "12") (pinfunction "12_12") (pintype "passive"))
    )
    (net (code "63") (name "Net-(D52-Pad11)") (class "Default")
      (node (ref "D52") (pin "11") (pinfunction "11_11") (pintype "passive"))
      (node (ref "D68") (pin "12") (pinfunction "12_12") (pintype "passive"))
    )
    (net (code "64") (name "Net-(D53-Pad11)") (class "Default")
      (node (ref "D53") (pin "11") (pinfunction "11_11") (pintype "passive"))
      (node (ref "D69") (pin "12") (pinfunction "12_12") (pintype "passive"))
    )
    (net (code "65") (name "Net-(D54-Pad11)") (class "Default")
      (node (ref "D54") (pin "11") (pinfunction "11_11") (pintype "passive"))
      (node (ref "D70") (pin "12") (pinfunction "12_12") (pintype "passive"))
    )
    (net (code "66") (name "Net-(D55-Pad11)") (class "Default")
      (node (ref "D55") (pin "11") (pinfunction "11_11") (pintype "passive"))
      (node (ref "D71") (pin "12") (pinfunction "12_12") (pintype "passive"))
    )
    (net (code "67") (name "Net-(D56-Pad11)") (class "Default")
      (node (ref "D56") (pin "11") (pinfunction "11_11") (pintype "passive"))
      (node (ref "D72") (pin "12") (pinfunction "12_12") (pintype "passive"))
    )
    (net (code "68") (name "Net-(D57-Pad11)") (class "Default")
      (node (ref "D57") (pin "11") (pinfunction "11_11") (pintype "passive"))
      (node (ref "D73") (pin "12") (pinfunction "12_12") (pintype "passive"))
    )
    (net (code "69") (name "Net-(D58-Pad11)") (class "Default")
      (node (ref "D58") (pin "11") (pinfunction "11_11") (pintype "passive"))
      (node (ref "D74") (pin "12") (pinfunction "12_12") (pintype "passive"))
    )
    (net (code "70") (name "Net-(D59-Pad11)") (class "Default")
      (node (ref "D59") (pin "11") (pinfunction "11_11") (pintype "passive"))
      (node (ref "D75") (pin "12") (pinfunction "12_12") (pintype "passive"))
    )
    (net (code "71") (name "Net-(D60-Pad11)") (class "Default")
      (node (ref "D60") (pin "11") (pinfunction "11_11") (pintype "passive"))
      (node (ref "D76") (pin "12") (pinfunction "12_12") (pintype "passive"))
    )
    (net (code "72") (name "Net-(D61-Pad11)") (class "Default")
      (node (ref "D61") (pin "11") (pinfunction "11_11") (pintype "passive"))
      (node (ref "D77") (pin "12") (pinfunction "12_12") (pintype "passive"))
    )
    (net (code "73") (name "Net-(D62-Pad11)") (class "Default")
      (node (ref "D62") (pin "11") (pinfunction "11_11") (pintype "passive"))
      (node (ref "D78") (pin "12") (pinfunction "12_12") (pintype "passive"))
    )
    (net (code "74") (name "Net-(D63-Pad11)") (class "Default")
      (node (ref "D63") (pin "11") (pinfunction "11_11") (pintype "passive"))
      (node (ref "D79") (pin "12") (pinfunction "12_12") (pintype "passive"))
    )
    (net (code "75") (name "Net-(D64-Pad11)") (class "Default")
      (node (ref "D64") (pin "11") (pinfunction "11_11") (pintype "passive"))
      (node (ref "D80") (pin "12") (pinfunction "12_12") (pintype "passive"))
    )
    (net (code "76") (name "Net-(D65-Pad11)") (class "Default")
      (node (ref "D65") (pin "11") (pinfunction "11_11") (pintype "passive"))
      (node (ref "D81") (pin "12") (pinfunction "12_12") (pintype "passive"))
    )
    (net (code "77") (name "Net-(D66-Pad11)") (class "Default")
      (node (ref "D66") (pin "11") (pinfunction "11_11") (pintype "passive"))
      (node (ref "D82") (pin "12") (pinfunction "12_12") (pintype "passive"))
    )
    (net (code "78") (name "Net-(D67-Pad11)") (class "Default")
      (node (ref "D67") (pin "11") (pinfunction "11_11") (pintype "passive"))
      (node (ref "R32") (pin "48") (pinfunction "48_48") (pintype "passive"))
    )
    (net (code "79") (name "Net-(D68-Pad11)") (class "Default")
      (node (ref "D68") (pin "11") (pinfunction "11_11") (pintype "passive"))
      (node (ref "R33") (pin "48") (pinfunction "48_48") (pintype "passive"))
    )
    (net (code "80") (name "Net-(D69-Pad11)") (class "Default")
      (node (ref "D69") (pin "11") (pinfunction "11_11") (pintype "passive"))
      (node (ref "R34") (pin "48") (pinfunction "48_48") (pintype "passive"))
    )
    (net (code "81") (name "Net-(D70-Pad11)") (class "Default")
      (node (ref "D70") (pin "11") (pinfunction "11_11") (pintype "passive"))
      (node (ref "R35") (pin "48") (pinfunction "48_48") (pintype "passive"))
    )
    (net (code "82") (name "Net-(D71-Pad11)") (class "Default")
      (node (ref "D71") (pin "11") (pinfunction "11_11") (pintype "passive"))
      (node (ref "R36") (pin "48") (pinfunction "48_48") (pintype "passive"))
    )
    (net (code "83") (name "Net-(D72-Pad11)") (class "Default")
      (node (ref "D72") (pin "11") (pinfunction "11_11") (pintype "passive"))
      (node (ref "R37") (pin "48") (pinfunction "48_48") (pintype "passive"))
    )
    (net (code "84") (name "Net-(D73-Pad11)") (class "Default")
      (node (ref "D73") (pin "11") (pinfunction "11_11") (pintype "passive"))
      (node (ref "R38") (pin "48") (pinfunction "48_48") (pintype "passive"))
    )
    (net (code "85") (name "Net-(D74-Pad11)") (class "Default")
      (node (ref "D74") (pin "11") (pinfunction "11_11") (pintype "passive"))
      (node (ref "R39") (pin "48") (pinfunction "48_48") (pintype "passive"))
    )
    (net (code "86") (name "Net-(D75-Pad11)") (class "Default")
      (node (ref "D75") (pin "11") (pinfunction "11_11") (pintype "passive"))
      (node (ref "R40") (pin "48") (pinfunction "48_48") (pintype "passive"))
    )
    (net (code "87") (name "Net-(D76-Pad11)") (class "Default")
      (node (ref "D76") (pin "11") (pinfunction "11_11") (pintype "passive"))
      (node (ref "R41") (pin "48") (pinfunction "48_48") (pintype "passive"))
    )
    (net (code "88") (name "Net-(D77-Pad11)") (class "Default")
      (node (ref "D77") (pin "11") (pinfunction "11_11") (pintype "passive"))
      (node (ref "R42") (pin "48") (pinfunction "48_48") (pintype "passive"))
    )
    (net (code "89") (name "Net-(D78-Pad11)") (class "Default")
      (node (ref "D78") (pin "11") (pinfunction "11_11") (pintype "passive"))
      (node (ref "R43") (pin "48") (pinfunction "48_48") (pintype "passive"))
    )
    (net (code "90") (name "Net-(D79-Pad11)") (class "Default")
      (node (ref "D79") (pin "11") (pinfunction "11_11") (pintype "passive"))
      (node (ref "R44") (pin "48") (pinfunction "48_48") (pintype "passive"))
    )
    (net (code "91") (name "Net-(D80-Pad11)") (class "Default")
      (node (ref "D80") (pin "11") (pinfunction "11_11") (pintype "passive"))
      (node (ref "R45") (pin "48") (pinfunction "48_48") (pintype "passive"))
    )
    (net (code "92") (name "Net-(D81-Pad11)") (class "Default")
      (node (ref "D81") (pin "11") (pinfunction "11_11") (pintype "passive"))
      (node (ref "R46") (pin "48") (pinfunction "48_48") (pintype "passive"))
    )
    (net (code "93") (name "Net-(D82-Pad11)") (class "Default")
      (node (ref "D82") (pin "11") (pinfunction "11_11") (pintype "passive"))
      (node (ref "R47") (pin "48") (pinfunction "48_48") (pintype "passive"))
    )
  )
)
